# ZQS_PCB_Project.net
KiCad netlist of a schematic drawn in Altium Designer
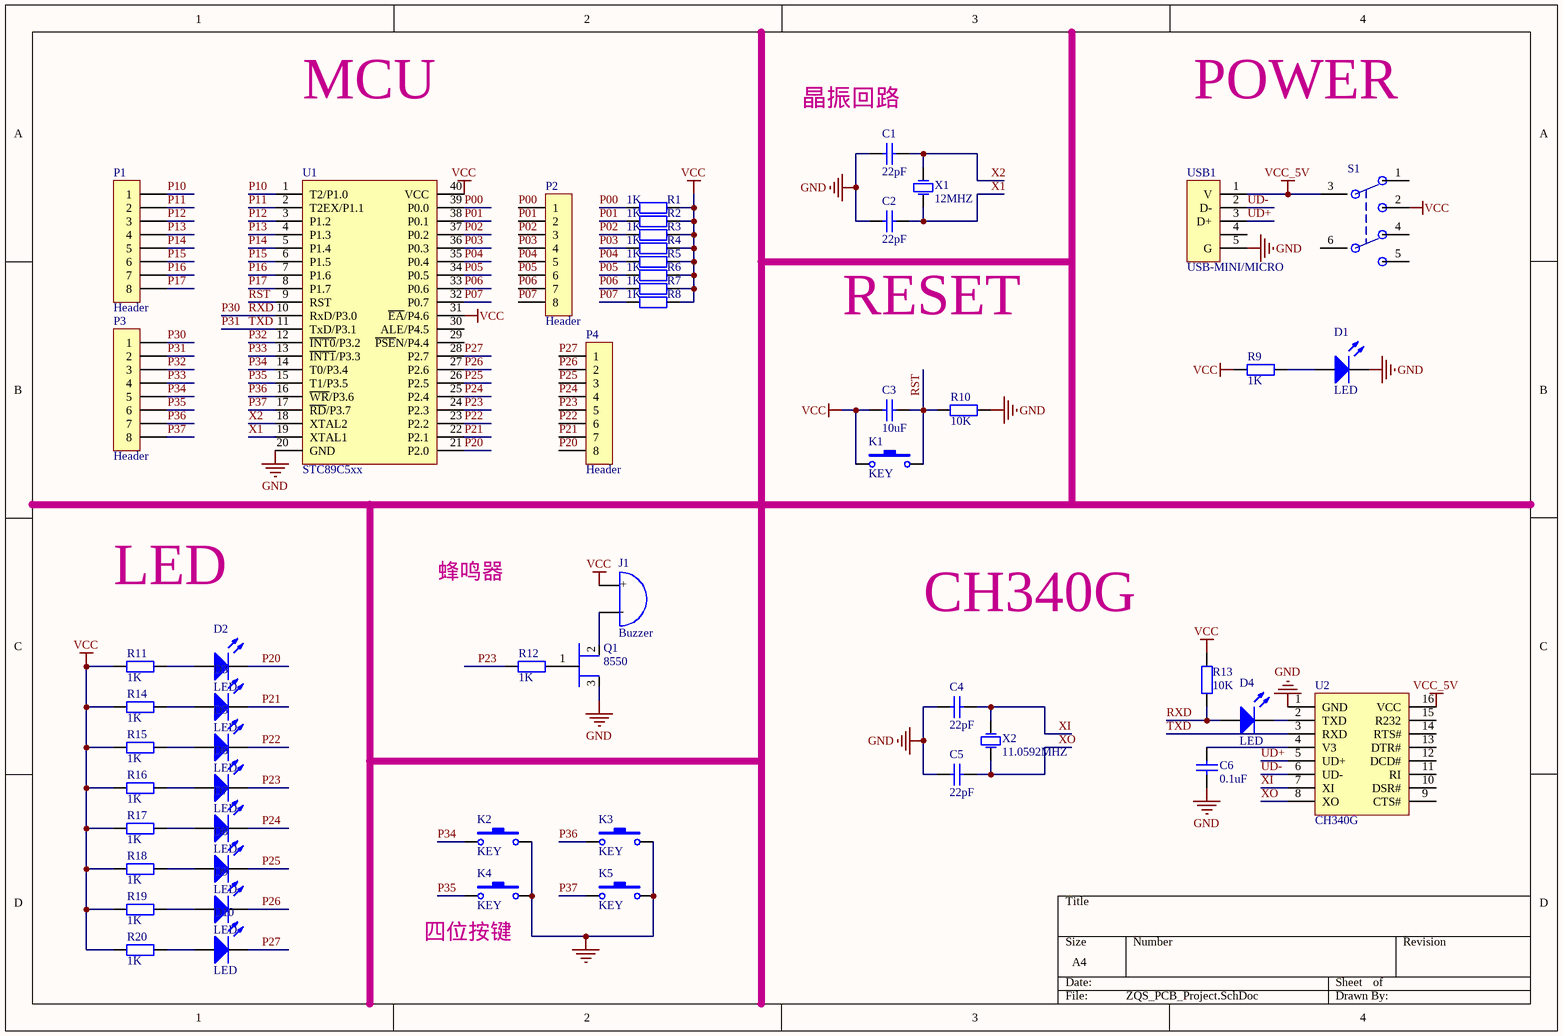
[diagram p0: ZQS_PCB_Project.SchDoc]

(export (version "E")
  (design (tool "Eeschema 10.0.6"))
  (components
    (comp (ref "C1") (value "22pF") (footprint "C0603") (libsource (lib "ZQS_Library") (part "CAP")))
    (comp (ref "C2") (value "22pF") (footprint "C0603") (libsource (lib "ZQS_Library") (part "CAP")))
    (comp (ref "C3") (value "10uF") (footprint "C0603") (libsource (lib "ZQS_Library") (part "CAP")))
    (comp (ref "C4") (value "22pF") (footprint "C0603") (libsource (lib "ZQS_Library") (part "CAP")))
    (comp (ref "C5") (value "22pF") (footprint "C0603") (libsource (lib "ZQS_Library") (part "CAP")))
    (comp (ref "C6") (value "0.1uF") (footprint "C0603") (libsource (lib "ZQS_Library") (part "CAP")))
    (comp (ref "D1") (value "LED") (footprint "LED-G") (libsource (lib "ZQS_Library") (part "LED")))
    (comp (ref "D2") (value "LED") (footprint "LED-B") (libsource (lib "ZQS_Library") (part "LED")))
    (comp (ref "D3") (value "LED") (footprint "LED-B") (libsource (lib "ZQS_Library") (part "LED")))
    (comp (ref "D4") (value "LED") (footprint "LED-G") (libsource (lib "ZQS_Library") (part "LED")))
    (comp (ref "D5") (value "LED") (footprint "LED-G") (libsource (lib "ZQS_Library") (part "LED")))
    (comp (ref "D6") (value "LED") (footprint "LED-G") (libsource (lib "ZQS_Library") (part "LED")))
    (comp (ref "D7") (value "LED") (footprint "LED-R") (libsource (lib "ZQS_Library") (part "LED")))
    (comp (ref "D8") (value "LED") (footprint "LED-R") (libsource (lib "ZQS_Library") (part "LED")))
    (comp (ref "D9") (value "LED") (footprint "LED-Y") (libsource (lib "ZQS_Library") (part "LED")))
    (comp (ref "D10") (value "LED") (footprint "LED-Y") (libsource (lib "ZQS_Library") (part "LED")))
    (comp (ref "J1") (value "Buzzer") (footprint "Buzzer") (libsource (lib "ZQS_Library") (part "Buzzer")))
    (comp (ref "K1") (value "KEY") (footprint "KEY") (libsource (lib "ZQS_Library") (part "KEY")))
    (comp (ref "K2") (value "KEY") (footprint "KEY") (libsource (lib "ZQS_Library") (part "KEY")))
    (comp (ref "K3") (value "KEY") (footprint "KEY") (libsource (lib "ZQS_Library") (part "KEY")))
    (comp (ref "K4") (value "KEY") (footprint "KEY") (libsource (lib "ZQS_Library") (part "KEY")))
    (comp (ref "K5") (value "KEY") (footprint "KEY") (libsource (lib "ZQS_Library") (part "KEY")))
    (comp (ref "P1") (value "Header") (footprint "HDR2.54-M-LI-8P") (libsource (lib "") (part "Header1x8_1")))
    (comp (ref "P2")
      (value "Header")
      (footprint "HDR2.54-M-LI-8P")
      (libsource (lib "ZQS_Library") (part "Header1x8"))
    )
    (comp (ref "P3") (value "Header") (footprint "HDR2.54-M-LI-8P") (libsource (lib "") (part "Header1x8_1")))
    (comp (ref "P4")
      (value "Header")
      (footprint "HDR2.54-M-LI-8P")
      (libsource (lib "ZQS_Library") (part "Header1x8"))
    )
    (comp (ref "Q1") (value "8550") (footprint "SOT-23-3") (libsource (lib "ZQS_Library") (part "Triode-3")))
    (comp (ref "R1") (value "1K") (footprint "R0603") (libsource (lib "ZQS_Library") (part "RES")))
    (comp (ref "R2") (value "1K") (footprint "R0603") (libsource (lib "ZQS_Library") (part "RES")))
    (comp (ref "R3") (value "1K") (footprint "R0603") (libsource (lib "ZQS_Library") (part "RES")))
    (comp (ref "R4") (value "1K") (footprint "R0603") (libsource (lib "ZQS_Library") (part "RES")))
    (comp (ref "R5") (value "1K") (footprint "R0603") (libsource (lib "ZQS_Library") (part "RES")))
    (comp (ref "R6") (value "1K") (footprint "R0603") (libsource (lib "ZQS_Library") (part "RES")))
    (comp (ref "R7") (value "1K") (footprint "R0603") (libsource (lib "ZQS_Library") (part "RES")))
    (comp (ref "R8") (value "1K") (footprint "R0603") (libsource (lib "ZQS_Library") (part "RES")))
    (comp (ref "R9") (value "1K") (footprint "R0603") (libsource (lib "ZQS_Library") (part "RES")))
    (comp (ref "R10") (value "10K") (footprint "R0603") (libsource (lib "ZQS_Library") (part "RES")))
    (comp (ref "R11") (value "1K") (footprint "R0603") (libsource (lib "ZQS_Library") (part "RES")))
    (comp (ref "R12") (value "1K") (footprint "R0603") (libsource (lib "ZQS_Library") (part "RES")))
    (comp (ref "R13") (value "10K") (footprint "R0603") (libsource (lib "") (part "RES_1")))
    (comp (ref "R14") (value "1K") (footprint "R0603") (libsource (lib "ZQS_Library") (part "RES")))
    (comp (ref "R15") (value "1K") (footprint "R0603") (libsource (lib "ZQS_Library") (part "RES")))
    (comp (ref "R16") (value "1K") (footprint "R0603") (libsource (lib "ZQS_Library") (part "RES")))
    (comp (ref "R17") (value "1K") (footprint "R0603") (libsource (lib "ZQS_Library") (part "RES")))
    (comp (ref "R18") (value "1K") (footprint "R0603") (libsource (lib "ZQS_Library") (part "RES")))
    (comp (ref "R19") (value "1K") (footprint "R0603") (libsource (lib "ZQS_Library") (part "RES")))
    (comp (ref "R20") (value "1K") (footprint "R0603") (libsource (lib "ZQS_Library") (part "RES")))
    (comp (ref "S1")
      (value "~")
      (footprint "swtich-6pin")
      (libsource (lib "ZQS_Library") (part "SWITCH-6PIN"))
    )
    (comp (ref "U1")
      (value "STC89C5xx")
      (footprint "STC89C5X")
      (libsource (lib "ZQS_Library") (part "STC89C5xx"))
    )
    (comp (ref "U2")
      (value "CH340G")
      (footprint "SOIC-16_150mil")
      (libsource (lib "ZQS_Library") (part "CH340G"))
    )
    (comp (ref "USB1")
      (value "USB-MINI/MICRO")
      (footprint "USB-MICRO2")
      (libsource (lib "ZQS_Library") (part "USB-MICRO"))
    )
    (comp (ref "X1") (value "12MHZ") (footprint "XTAL_HC49SMD") (libsource (lib "ZQS_Library") (part "XTAL")))
    (comp (ref "X2")
      (value "11.0592MHZ")
      (footprint "XTAL_HC49SMD")
      (libsource (lib "ZQS_Library") (part "XTAL"))
    )
  )
  (nets
    (net (code "1") (name "/P00") (class "Default")
      (node (ref "P2") (pin "1") (pinfunction "1_1") (pintype "passive"))
      (node (ref "R1") (pin "1") (pinfunction "1_1") (pintype "passive"))
      (node (ref "U1") (pin "39") (pinfunction "P0.0_39") (pintype "passive"))
    )
    (net (code "2") (name "/P01") (class "Default")
      (node (ref "P2") (pin "2") (pinfunction "2_2") (pintype "passive"))
      (node (ref "R2") (pin "1") (pinfunction "1_1") (pintype "passive"))
      (node (ref "U1") (pin "38") (pinfunction "P0.1_38") (pintype "passive"))
    )
    (net (code "3") (name "/P02") (class "Default")
      (node (ref "P2") (pin "3") (pinfunction "3_3") (pintype "passive"))
      (node (ref "R3") (pin "1") (pinfunction "1_1") (pintype "passive"))
      (node (ref "U1") (pin "37") (pinfunction "P0.2_37") (pintype "passive"))
    )
    (net (code "4") (name "/P03") (class "Default")
      (node (ref "P2") (pin "4") (pinfunction "4_4") (pintype "passive"))
      (node (ref "R4") (pin "1") (pinfunction "1_1") (pintype "passive"))
      (node (ref "U1") (pin "36") (pinfunction "P0.3_36") (pintype "passive"))
    )
    (net (code "5") (name "/P04") (class "Default")
      (node (ref "P2") (pin "5") (pinfunction "5_5") (pintype "passive"))
      (node (ref "R5") (pin "1") (pinfunction "1_1") (pintype "passive"))
      (node (ref "U1") (pin "35") (pinfunction "P0.4_35") (pintype "passive"))
    )
    (net (code "6") (name "/P05") (class "Default")
      (node (ref "P2") (pin "6") (pinfunction "6_6") (pintype "passive"))
      (node (ref "R6") (pin "1") (pinfunction "1_1") (pintype "passive"))
      (node (ref "U1") (pin "34") (pinfunction "P0.5_34") (pintype "passive"))
    )
    (net (code "7") (name "/P06") (class "Default")
      (node (ref "P2") (pin "7") (pinfunction "7_7") (pintype "passive"))
      (node (ref "R7") (pin "1") (pinfunction "1_1") (pintype "passive"))
      (node (ref "U1") (pin "33") (pinfunction "P0.6_33") (pintype "passive"))
    )
    (net (code "8") (name "/P07") (class "Default")
      (node (ref "P2") (pin "8") (pinfunction "8_8") (pintype "passive"))
      (node (ref "R8") (pin "1") (pinfunction "1_1") (pintype "passive"))
      (node (ref "U1") (pin "32") (pinfunction "P0.7_32") (pintype "passive"))
    )
    (net (code "9") (name "/P10") (class "Default")
      (node (ref "P1") (pin "1") (pinfunction "1_1") (pintype "passive"))
      (node (ref "U1") (pin "1") (pinfunction "T2/P1.0_1") (pintype "passive"))
    )
    (net (code "10") (name "/P11") (class "Default")
      (node (ref "P1") (pin "2") (pinfunction "2_2") (pintype "passive"))
      (node (ref "U1") (pin "2") (pinfunction "T2EX/P1.1_2") (pintype "passive"))
    )
    (net (code "11") (name "/P12") (class "Default")
      (node (ref "P1") (pin "3") (pinfunction "3_3") (pintype "passive"))
      (node (ref "U1") (pin "3") (pinfunction "P1.2_3") (pintype "passive"))
    )
    (net (code "12") (name "/P13") (class "Default")
      (node (ref "P1") (pin "4") (pinfunction "4_4") (pintype "passive"))
      (node (ref "U1") (pin "4") (pinfunction "P1.3_4") (pintype "passive"))
    )
    (net (code "13") (name "/P14") (class "Default")
      (node (ref "P1") (pin "5") (pinfunction "5_5") (pintype "passive"))
      (node (ref "U1") (pin "5") (pinfunction "P1.4_5") (pintype "passive"))
    )
    (net (code "14") (name "/P15") (class "Default")
      (node (ref "P1") (pin "6") (pinfunction "6_6") (pintype "passive"))
      (node (ref "U1") (pin "6") (pinfunction "P1.5_6") (pintype "passive"))
    )
    (net (code "15") (name "/P16") (class "Default")
      (node (ref "P1") (pin "7") (pinfunction "7_7") (pintype "passive"))
      (node (ref "U1") (pin "7") (pinfunction "P1.6_7") (pintype "passive"))
    )
    (net (code "16") (name "/P17") (class "Default")
      (node (ref "P1") (pin "8") (pinfunction "8_8") (pintype "passive"))
      (node (ref "U1") (pin "8") (pinfunction "P1.7_8") (pintype "passive"))
    )
    (net (code "17") (name "/P20") (class "Default")
      (node (ref "D2") (pin "2") (pinfunction "K_2") (pintype "passive"))
      (node (ref "P4") (pin "8") (pinfunction "8_8") (pintype "passive"))
      (node (ref "U1") (pin "21") (pinfunction "P2.0_21") (pintype "passive"))
    )
    (net (code "18") (name "/P21") (class "Default")
      (node (ref "D3") (pin "2") (pinfunction "K_2") (pintype "passive"))
      (node (ref "P4") (pin "7") (pinfunction "7_7") (pintype "passive"))
      (node (ref "U1") (pin "22") (pinfunction "P2.1_22") (pintype "passive"))
    )
    (net (code "19") (name "/P22") (class "Default")
      (node (ref "D5") (pin "2") (pinfunction "K_2") (pintype "passive"))
      (node (ref "P4") (pin "6") (pinfunction "6_6") (pintype "passive"))
      (node (ref "U1") (pin "23") (pinfunction "P2.2_23") (pintype "passive"))
    )
    (net (code "20") (name "/P23") (class "Default")
      (node (ref "D6") (pin "2") (pinfunction "K_2") (pintype "passive"))
      (node (ref "P4") (pin "5") (pinfunction "5_5") (pintype "passive"))
      (node (ref "R12") (pin "1") (pinfunction "1_1") (pintype "passive"))
      (node (ref "U1") (pin "24") (pinfunction "P2.3_24") (pintype "passive"))
    )
    (net (code "21") (name "/P24") (class "Default")
      (node (ref "D7") (pin "2") (pinfunction "K_2") (pintype "passive"))
      (node (ref "P4") (pin "4") (pinfunction "4_4") (pintype "passive"))
      (node (ref "U1") (pin "25") (pinfunction "P2.4_25") (pintype "passive"))
    )
    (net (code "22") (name "/P25") (class "Default")
      (node (ref "D8") (pin "2") (pinfunction "K_2") (pintype "passive"))
      (node (ref "P4") (pin "3") (pinfunction "3_3") (pintype "passive"))
      (node (ref "U1") (pin "26") (pinfunction "P2.5_26") (pintype "passive"))
    )
    (net (code "23") (name "/P26") (class "Default")
      (node (ref "D9") (pin "2") (pinfunction "K_2") (pintype "passive"))
      (node (ref "P4") (pin "2") (pinfunction "2_2") (pintype "passive"))
      (node (ref "U1") (pin "27") (pinfunction "P2.6_27") (pintype "passive"))
    )
    (net (code "24") (name "/P27") (class "Default")
      (node (ref "D10") (pin "2") (pinfunction "K_2") (pintype "passive"))
      (node (ref "P4") (pin "1") (pinfunction "1_1") (pintype "passive"))
      (node (ref "U1") (pin "28") (pinfunction "P2.7_28") (pintype "passive"))
    )
    (net (code "25") (name "/P30") (class "Default")
      (node (ref "D4") (pin "1") (pinfunction "A_1") (pintype "passive"))
      (node (ref "P3") (pin "1") (pinfunction "1_1") (pintype "passive"))
      (node (ref "R13") (pin "1") (pinfunction "1_1") (pintype "passive"))
      (node (ref "U1") (pin "10") (pinfunction "RxD/P3.0_10") (pintype "passive"))
    )
    (net (code "26") (name "/P31") (class "Default")
      (node (ref "P3") (pin "2") (pinfunction "2_2") (pintype "passive"))
      (node (ref "U1") (pin "11") (pinfunction "TxD/P3.1_11") (pintype "passive"))
      (node (ref "U2") (pin "3") (pinfunction "RXD_3") (pintype "passive"))
    )
    (net (code "27") (name "/P32") (class "Default")
      (node (ref "P3") (pin "3") (pinfunction "3_3") (pintype "passive"))
      (node (ref "U1") (pin "12") (pinfunction "~{INT0}/P3.2_12") (pintype "passive"))
    )
    (net (code "28") (name "/P33") (class "Default")
      (node (ref "P3") (pin "4") (pinfunction "4_4") (pintype "passive"))
      (node (ref "U1") (pin "13") (pinfunction "~{INT1}/P3.3_13") (pintype "passive"))
    )
    (net (code "29") (name "/P34") (class "Default")
      (node (ref "K2") (pin "1") (pinfunction "1_1") (pintype "passive"))
      (node (ref "P3") (pin "5") (pinfunction "5_5") (pintype "passive"))
      (node (ref "U1") (pin "14") (pinfunction "T0/P3.4_14") (pintype "passive"))
    )
    (net (code "30") (name "/P35") (class "Default")
      (node (ref "K4") (pin "1") (pinfunction "1_1") (pintype "passive"))
      (node (ref "P3") (pin "6") (pinfunction "6_6") (pintype "passive"))
      (node (ref "U1") (pin "15") (pinfunction "T1/P3.5_15") (pintype "passive"))
    )
    (net (code "31") (name "/P36") (class "Default")
      (node (ref "K3") (pin "1") (pinfunction "1_1") (pintype "passive"))
      (node (ref "P3") (pin "7") (pinfunction "7_7") (pintype "passive"))
      (node (ref "U1") (pin "16") (pinfunction "~{WR}/P3.6_16") (pintype "passive"))
    )
    (net (code "32") (name "/P37") (class "Default")
      (node (ref "K5") (pin "1") (pinfunction "1_1") (pintype "passive"))
      (node (ref "P3") (pin "8") (pinfunction "8_8") (pintype "passive"))
      (node (ref "U1") (pin "17") (pinfunction "~{RD}/P3.7_17") (pintype "passive"))
    )
    (net (code "33") (name "/RST") (class "Default")
      (node (ref "C3") (pin "2") (pinfunction "2_2") (pintype "passive"))
      (node (ref "K1") (pin "2") (pinfunction "2_2") (pintype "passive"))
      (node (ref "R10") (pin "1") (pinfunction "1_1") (pintype "passive"))
      (node (ref "U1") (pin "9") (pinfunction "RST_9") (pintype "passive"))
    )
    (net (code "34") (name "/UD+") (class "Default")
      (node (ref "U2") (pin "5") (pinfunction "UD+_5") (pintype "passive"))
      (node (ref "USB1") (pin "3") (pinfunction "D+_3") (pintype "passive"))
    )
    (net (code "35") (name "/UD-") (class "Default")
      (node (ref "U2") (pin "6") (pinfunction "UD-_6") (pintype "passive"))
      (node (ref "USB1") (pin "2") (pinfunction "D-_2") (pintype "passive"))
    )
    (net (code "36") (name "/X1") (class "Default")
      (node (ref "C2") (pin "2") (pinfunction "2_2") (pintype "passive"))
      (node (ref "U1") (pin "19") (pinfunction "XTAL1_19") (pintype "passive"))
      (node (ref "X1") (pin "1") (pinfunction "OSC1_1") (pintype "passive"))
    )
    (net (code "37") (name "/X2") (class "Default")
      (node (ref "C1") (pin "2") (pinfunction "2_2") (pintype "passive"))
      (node (ref "U1") (pin "18") (pinfunction "XTAL2_18") (pintype "passive"))
      (node (ref "X1") (pin "2") (pinfunction "OSC2_2") (pintype "passive"))
    )
    (net (code "38") (name "/XI") (class "Default")
      (node (ref "C4") (pin "1") (pinfunction "1_1") (pintype "passive"))
      (node (ref "U2") (pin "7") (pinfunction "XI_7") (pintype "passive"))
      (node (ref "X2") (pin "1") (pinfunction "OSC1_1") (pintype "passive"))
    )
    (net (code "39") (name "/XO") (class "Default")
      (node (ref "C5") (pin "1") (pinfunction "1_1") (pintype "passive"))
      (node (ref "U2") (pin "8") (pinfunction "XO_8") (pintype "passive"))
      (node (ref "X2") (pin "2") (pinfunction "OSC2_2") (pintype "passive"))
    )
    (net (code "40") (name "GND") (class "Default")
      (node (ref "C1") (pin "1") (pinfunction "1_1") (pintype "passive"))
      (node (ref "C2") (pin "1") (pinfunction "1_1") (pintype "passive"))
      (node (ref "C4") (pin "2") (pinfunction "2_2") (pintype "passive"))
      (node (ref "C5") (pin "2") (pinfunction "2_2") (pintype "passive"))
      (node (ref "C6") (pin "1") (pinfunction "1_1") (pintype "passive"))
      (node (ref "D1") (pin "2") (pinfunction "K_2") (pintype "passive"))
      (node (ref "K2") (pin "2") (pinfunction "2_2") (pintype "passive"))
      (node (ref "K3") (pin "2") (pinfunction "2_2") (pintype "passive"))
      (node (ref "K4") (pin "2") (pinfunction "2_2") (pintype "passive"))
      (node (ref "K5") (pin "2") (pinfunction "2_2") (pintype "passive"))
      (node (ref "Q1") (pin "3") (pinfunction "3_3") (pintype "passive"))
      (node (ref "R10") (pin "2") (pinfunction "2_2") (pintype "passive"))
      (node (ref "U1") (pin "20") (pinfunction "GND_20") (pintype "passive"))
      (node (ref "U2") (pin "1") (pinfunction "GND_1") (pintype "passive"))
      (node (ref "USB1") (pin "5") (pinfunction "G_5") (pintype "passive"))
    )
    (net (code "41") (name "Net-(D1-A)") (class "Default")
      (node (ref "D1") (pin "1") (pinfunction "A_1") (pintype "passive"))
      (node (ref "R9") (pin "2") (pinfunction "2_2") (pintype "passive"))
    )
    (net (code "42") (name "Net-(D2-A)") (class "Default")
      (node (ref "D2") (pin "1") (pinfunction "A_1") (pintype "passive"))
      (node (ref "R11") (pin "2") (pinfunction "2_2") (pintype "passive"))
    )
    (net (code "43") (name "Net-(D3-A)") (class "Default")
      (node (ref "D3") (pin "1") (pinfunction "A_1") (pintype "passive"))
      (node (ref "R14") (pin "2") (pinfunction "2_2") (pintype "passive"))
    )
    (net (code "44") (name "Net-(D4-K)") (class "Default")
      (node (ref "D4") (pin "2") (pinfunction "K_2") (pintype "passive"))
      (node (ref "U2") (pin "2") (pinfunction "TXD_2") (pintype "passive"))
    )
    (net (code "45") (name "Net-(D5-A)") (class "Default")
      (node (ref "D5") (pin "1") (pinfunction "A_1") (pintype "passive"))
      (node (ref "R15") (pin "2") (pinfunction "2_2") (pintype "passive"))
    )
    (net (code "46") (name "Net-(D6-A)") (class "Default")
      (node (ref "D6") (pin "1") (pinfunction "A_1") (pintype "passive"))
      (node (ref "R16") (pin "2") (pinfunction "2_2") (pintype "passive"))
    )
    (net (code "47") (name "Net-(D7-A)") (class "Default")
      (node (ref "D7") (pin "1") (pinfunction "A_1") (pintype "passive"))
      (node (ref "R17") (pin "2") (pinfunction "2_2") (pintype "passive"))
    )
    (net (code "48") (name "Net-(D8-A)") (class "Default")
      (node (ref "D8") (pin "1") (pinfunction "A_1") (pintype "passive"))
      (node (ref "R18") (pin "2") (pinfunction "2_2") (pintype "passive"))
    )
    (net (code "49") (name "Net-(D9-A)") (class "Default")
      (node (ref "D9") (pin "1") (pinfunction "A_1") (pintype "passive"))
      (node (ref "R19") (pin "2") (pinfunction "2_2") (pintype "passive"))
    )
    (net (code "50") (name "Net-(D10-A)") (class "Default")
      (node (ref "D10") (pin "1") (pinfunction "A_1") (pintype "passive"))
      (node (ref "R20") (pin "2") (pinfunction "2_2") (pintype "passive"))
    )
    (net (code "51") (name "Net-(J1-B)") (class "Default")
      (node (ref "J1") (pin "2") (pinfunction "B_2") (pintype "passive"))
      (node (ref "Q1") (pin "2") (pinfunction "2_2") (pintype "passive"))
    )
    (net (code "52") (name "Net-(Q1-Pad1)") (class "Default")
      (node (ref "Q1") (pin "1") (pinfunction "1_1") (pintype "passive"))
      (node (ref "R12") (pin "2") (pinfunction "2_2") (pintype "passive"))
    )
    (net (code "53") (name "Net-(U2-V3)") (class "Default")
      (node (ref "C6") (pin "2") (pinfunction "2_2") (pintype "passive"))
      (node (ref "U2") (pin "4") (pinfunction "V3_4") (pintype "passive"))
    )
    (net (code "54") (name "VCC") (class "Default")
      (node (ref "C3") (pin "1") (pinfunction "1_1") (pintype "passive"))
      (node (ref "J1") (pin "1") (pinfunction "A_1") (pintype "passive"))
      (node (ref "K1") (pin "1") (pinfunction "1_1") (pintype "passive"))
      (node (ref "R1") (pin "2") (pinfunction "2_2") (pintype "passive"))
      (node (ref "R11") (pin "1") (pinfunction "1_1") (pintype "passive"))
      (node (ref "R13") (pin "2") (pinfunction "2_2") (pintype "passive"))
      (node (ref "R14") (pin "1") (pinfunction "1_1") (pintype "passive"))
      (node (ref "R15") (pin "1") (pinfunction "1_1") (pintype "passive"))
      (node (ref "R16") (pin "1") (pinfunction "1_1") (pintype "passive"))
      (node (ref "R17") (pin "1") (pinfunction "1_1") (pintype "passive"))
      (node (ref "R18") (pin "1") (pinfunction "1_1") (pintype "passive"))
      (node (ref "R19") (pin "1") (pinfunction "1_1") (pintype "passive"))
      (node (ref "R2") (pin "2") (pinfunction "2_2") (pintype "passive"))
      (node (ref "R20") (pin "1") (pinfunction "1_1") (pintype "passive"))
      (node (ref "R3") (pin "2") (pinfunction "2_2") (pintype "passive"))
      (node (ref "R4") (pin "2") (pinfunction "2_2") (pintype "passive"))
      (node (ref "R5") (pin "2") (pinfunction "2_2") (pintype "passive"))
      (node (ref "R6") (pin "2") (pinfunction "2_2") (pintype "passive"))
      (node (ref "R7") (pin "2") (pinfunction "2_2") (pintype "passive"))
      (node (ref "R8") (pin "2") (pinfunction "2_2") (pintype "passive"))
      (node (ref "R9") (pin "1") (pinfunction "1_1") (pintype "passive"))
      (node (ref "S1") (pin "2") (pintype "passive"))
      (node (ref "U1") (pin "31") (pinfunction "~{EA}/P4.6_31") (pintype "passive"))
      (node (ref "U1") (pin "40") (pinfunction "VCC_40") (pintype "passive"))
    )
    (net (code "55") (name "VCC_5V") (class "Default")
      (node (ref "S1") (pin "3") (pintype "passive"))
      (node (ref "U2") (pin "16") (pinfunction "VCC_16") (pintype "passive"))
      (node (ref "USB1") (pin "1") (pinfunction "V_1") (pintype "passive"))
    )
    (net (code "56") (name "unconnected-(S1-Pad1)") (class "Default")
      (node (ref "S1") (pin "1") (pintype "passive"))
    )
    (net (code "57") (name "unconnected-(S1-Pad4)") (class "Default")
      (node (ref "S1") (pin "4") (pintype "passive"))
    )
    (net (code "58") (name "unconnected-(S1-Pad5)") (class "Default")
      (node (ref "S1") (pin "5") (pintype "passive"))
    )
    (net (code "59") (name "unconnected-(S1-Pad6)") (class "Default")
      (node (ref "S1") (pin "6") (pintype "passive"))
    )
    (net (code "60") (name "unconnected-(U1-ALE{slash}P4.5-Pad30)") (class "Default")
      (node (ref "U1") (pin "30") (pinfunction "ALE/P4.5_30") (pintype "passive"))
    )
    (net (code "61") (name "unconnected-(U1-~{PSE}N{slash}P4.4-Pad29)") (class "Default")
      (node (ref "U1") (pin "29") (pinfunction "~{PSE}N/P4.4_29") (pintype "passive"))
    )
    (net (code "62") (name "unconnected-(U2-CTS#-Pad9)") (class "Default")
      (node (ref "U2") (pin "9") (pinfunction "CTS#_9") (pintype "passive"))
    )
    (net (code "63") (name "unconnected-(U2-DCD#-Pad12)") (class "Default")
      (node (ref "U2") (pin "12") (pinfunction "DCD#_12") (pintype "passive"))
    )
    (net (code "64") (name "unconnected-(U2-DSR#-Pad10)") (class "Default")
      (node (ref "U2") (pin "10") (pinfunction "DSR#_10") (pintype "passive"))
    )
    (net (code "65") (name "unconnected-(U2-DTR#-Pad13)") (class "Default")
      (node (ref "U2") (pin "13") (pinfunction "DTR#_13") (pintype "passive"))
    )
    (net (code "66") (name "unconnected-(U2-R232-Pad15)") (class "Default")
      (node (ref "U2") (pin "15") (pinfunction "R232_15") (pintype "passive"))
    )
    (net (code "67") (name "unconnected-(U2-RI-Pad11)") (class "Default")
      (node (ref "U2") (pin "11") (pinfunction "RI_11") (pintype "passive"))
    )
    (net (code "68") (name "unconnected-(U2-RTS#-Pad14)") (class "Default")
      (node (ref "U2") (pin "14") (pinfunction "RTS#_14") (pintype "passive"))
    )
    (net (code "69") (name "unconnected-(USB1-Pad4)") (class "Default")
      (node (ref "USB1") (pin "4") (pintype "passive"))
    )
  )
)
